# HS_SW.net
KiCad netlist of a schematic drawn in Altium Designer
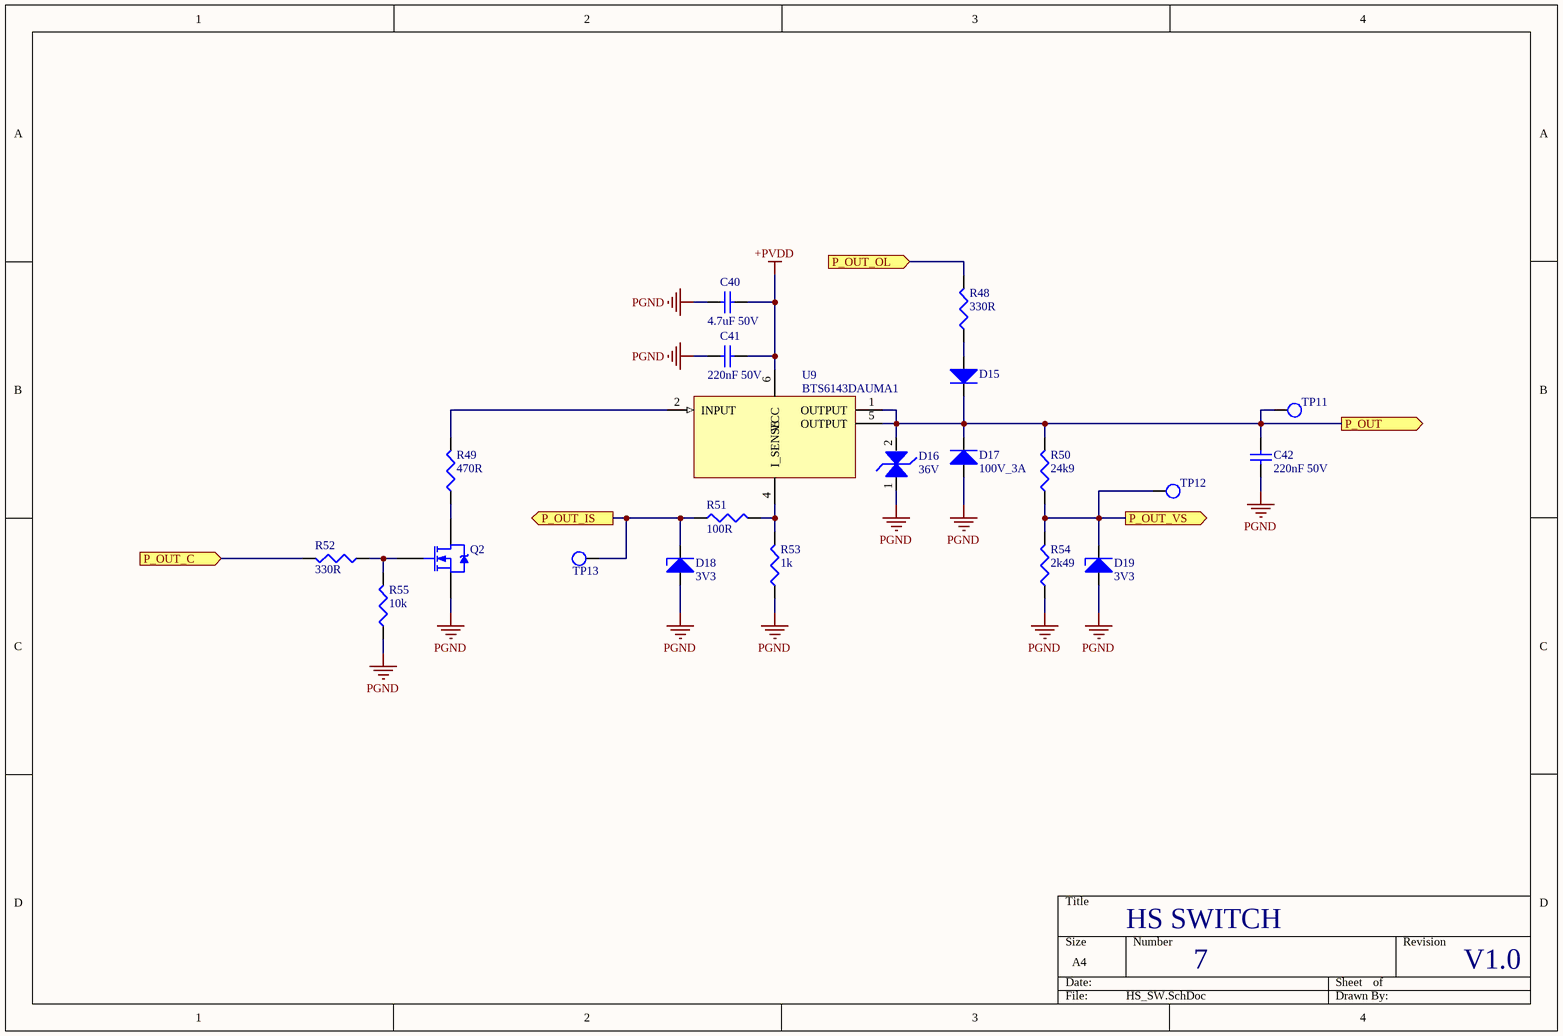
[diagram p0: HS_SW.SchDoc]

(export (version "E")
  (design (tool "Eeschema 10.0.6"))
  (components
    (comp (ref "C40")
      (value "4.7uF 50V")
      (footprint "CAP1206")
      (description "CAP CER 4.7UF 50V %20 X7R 1206")
      (libsource (lib "CAP_Library") (part "CAP1206_4.7uF"))
    )
    (comp (ref "C41")
      (value "220nF 50V")
      (footprint "CAP1206")
      (description "CAP CER 0.22UF 50V X7R 1206")
      (libsource (lib "CAP_Library") (part "CAP1206_220nF"))
    )
    (comp (ref "C42")
      (value "220nF 50V")
      (footprint "CAP1206")
      (description "CAP CER 0.22UF 50V X7R 1206")
      (libsource (lib "CAP_Library") (part "CAP1206_220nF"))
    )
    (comp (ref "D15")
      (value "100V 300mA")
      (footprint "SOD123_1N4148W-7-F")
      (description "DIODE GEN PURP 100V 300MA SOD123")
      (libsource (lib "DIODE_Library") (part "DIODE_1N4148W-7-F"))
    )
    (comp (ref "D16")
      (value "36V")
      (footprint "DO214AA")
      (description "TVS DIODE 36V DO214AA")
      (libsource (lib "DIODE_Library") (part "SMBJ36CA-TR_TVS_BI_DIR"))
    )
    (comp (ref "D17")
      (value "100V_3A")
      (footprint "DO-221A")
      (description "DIODE FRED 100V 3A DO-221AD")
      (libsource (lib "DIODE_Library") (part "FRED_VS-3EYH01-M3/H_100V_3A"))
    )
    (comp (ref "D18")
      (value "3V3")
      (footprint "SOD323")
      (description "DIODE ZENER 3.3V 300MW SOD323")
      (libsource (lib "DIODE_Library") (part "ZENER_3V3_MM3Z3V3T1G"))
    )
    (comp (ref "D19")
      (value "3V3")
      (footprint "SOD323")
      (description "DIODE ZENER 3.3V 300MW SOD323")
      (libsource (lib "DIODE_Library") (part "ZENER_3V3_MM3Z3V3T1G"))
    )
    (comp (ref "Q2")
      (value "60V 360mA")
      (footprint "SOT23_2N7002")
      (description "MOSFET N-CH 60V 0.36A SOT-23")
      (libsource (lib "Mosfet_Library") (part "2N7002P,215_NMOS_60V"))
    )
    (comp (ref "R48")
      (value "330R")
      (footprint "RES0603")
      (description "RES 330 OHM 1% 1/10W 0603")
      (libsource (lib "RES_Library") (part "RES0603_330R"))
    )
    (comp (ref "R49")
      (value "470R")
      (footprint "RES0603")
      (description "RES SMD 470 OHM 1% 1/10W 0603")
      (libsource (lib "RES_Library") (part "RES0603_470R"))
    )
    (comp (ref "R50")
      (value "24k9")
      (footprint "RES0603")
      (description "RES SMD 24.9K OHM 1% 1/10W 0603")
      (libsource (lib "RES_Library") (part "RES0603_24k9"))
    )
    (comp (ref "R51")
      (value "100R")
      (footprint "RES0603")
      (description "RES SMD 100R OHM 1% 1/10W 0603")
      (libsource (lib "RES_Library") (part "RES0603_100R"))
    )
    (comp (ref "R52")
      (value "330R")
      (footprint "RES0603")
      (description "RES 330 OHM 1% 1/10W 0603")
      (libsource (lib "RES_Library") (part "RES0603_330R"))
    )
    (comp (ref "R53")
      (value "1k")
      (footprint "RES0603")
      (description "RES SMD 1K OHM 1% 1/10W 0603")
      (libsource (lib "RES_Library") (part "RES0603_1k"))
    )
    (comp (ref "R54")
      (value "2k49")
      (footprint "RES0603")
      (description "RES 2.49K OHM 1% 1/10W 0603")
      (libsource (lib "RES_Library") (part "RES0603_2k49"))
    )
    (comp (ref "R55")
      (value "10k")
      (footprint "RES0603")
      (description "RES SMD 10K OHM 5% 1/10W 0603")
      (libsource (lib "RES_Library") (part "RES0603_10k"))
    )
    (comp (ref "TP11")
      (value "TEST_POINT")
      (footprint "TEST_POINT_TH")
      (libsource (lib "MISC_Library") (part "TEST_POINT"))
    )
    (comp (ref "TP12")
      (value "TEST_POINT")
      (footprint "TEST_POINT_TH")
      (libsource (lib "MISC_Library") (part "TEST_POINT"))
    )
    (comp (ref "TP13")
      (value "TEST_POINT")
      (footprint "TEST_POINT_TH")
      (libsource (lib "MISC_Library") (part "TEST_POINT"))
    )
    (comp (ref "U9")
      (value "33A")
      (footprint "TO252-5")
      (description "IC HIGH SIDE PWR SWITCH DPAK-5")
      (fields (field (name "P/N") "BTS6143DAUMA1"))
      (libsource (lib "IC_Library") (part "PD_SW_BTS6143DAUMA1"))
    )
  )
  (nets
    (net (code "1") (name "+PVDD") (class "Default")
      (node (ref "C40") (pin "2") (pinfunction "2_2") (pintype "passive"))
      (node (ref "C41") (pin "1") (pinfunction "1_1") (pintype "passive"))
      (node (ref "U9") (pin "6") (pinfunction "VCC_6") (pintype "power_in"))
    )
    (net (code "2") (name "/P_OUT") (class "Default")
      (node (ref "C42") (pin "2") (pinfunction "2_2") (pintype "passive"))
      (node (ref "D15") (pin "2") (pinfunction "K_2") (pintype "passive"))
      (node (ref "D16") (pin "2") (pinfunction "2_2") (pintype "passive"))
      (node (ref "D17") (pin "1") (pinfunction "K_1") (pintype "passive"))
      (node (ref "R50") (pin "2") (pinfunction "2_2") (pintype "passive"))
      (node (ref "TP11") (pin "1") (pinfunction "1_1") (pintype "passive"))
      (node (ref "U9") (pin "1") (pinfunction "OUTPUT_1") (pintype "passive"))
      (node (ref "U9") (pin "5") (pinfunction "OUTPUT_5") (pintype "passive"))
    )
    (net (code "3") (name "/P_OUT_C") (class "Default")
      (node (ref "R52") (pin "2") (pinfunction "2_2") (pintype "passive"))
    )
    (net (code "4") (name "/P_OUT_IS") (class "Default")
      (node (ref "D18") (pin "1") (pinfunction "K_1") (pintype "passive"))
      (node (ref "R51") (pin "1") (pinfunction "1_1") (pintype "passive"))
      (node (ref "TP13") (pin "1") (pinfunction "1_1") (pintype "passive"))
    )
    (net (code "5") (name "/P_OUT_OL") (class "Default")
      (node (ref "R48") (pin "2") (pinfunction "2_2") (pintype "passive"))
    )
    (net (code "6") (name "/P_OUT_VS") (class "Default")
      (node (ref "D19") (pin "1") (pinfunction "K_1") (pintype "passive"))
      (node (ref "R50") (pin "1") (pinfunction "1_1") (pintype "passive"))
      (node (ref "R54") (pin "2") (pinfunction "2_2") (pintype "passive"))
      (node (ref "TP12") (pin "1") (pinfunction "1_1") (pintype "passive"))
    )
    (net (code "7") (name "Net-(D15-A)") (class "Default")
      (node (ref "D15") (pin "1") (pinfunction "A_1") (pintype "passive"))
      (node (ref "R48") (pin "1") (pinfunction "1_1") (pintype "passive"))
    )
    (net (code "8") (name "Net-(Q2-D)") (class "Default")
      (node (ref "Q2") (pin "3") (pinfunction "D_3") (pintype "passive"))
      (node (ref "R49") (pin "1") (pinfunction "1_1") (pintype "passive"))
    )
    (net (code "9") (name "Net-(Q2-G)") (class "Default")
      (node (ref "Q2") (pin "1") (pinfunction "G_1") (pintype "passive"))
      (node (ref "R52") (pin "1") (pinfunction "1_1") (pintype "passive"))
      (node (ref "R55") (pin "2") (pinfunction "2_2") (pintype "passive"))
    )
    (net (code "10") (name "Net-(U9-INPUT)") (class "Default")
      (node (ref "R49") (pin "2") (pinfunction "2_2") (pintype "passive"))
      (node (ref "U9") (pin "2") (pinfunction "INPUT_2") (pintype "input"))
    )
    (net (code "11") (name "Net-(U9-I_SENSE)") (class "Default")
      (node (ref "R51") (pin "2") (pinfunction "2_2") (pintype "passive"))
      (node (ref "R53") (pin "2") (pinfunction "2_2") (pintype "passive"))
      (node (ref "U9") (pin "4") (pinfunction "I_SENSE_4") (pintype "power_in"))
    )
    (net (code "12") (name "PGND") (class "Default")
      (node (ref "C40") (pin "1") (pinfunction "1_1") (pintype "passive"))
      (node (ref "C41") (pin "2") (pinfunction "2_2") (pintype "passive"))
      (node (ref "C42") (pin "1") (pinfunction "1_1") (pintype "passive"))
      (node (ref "D16") (pin "1") (pinfunction "1_1") (pintype "passive"))
      (node (ref "D17") (pin "2") (pinfunction "A_2") (pintype "passive"))
      (node (ref "D18") (pin "2") (pinfunction "A_2") (pintype "passive"))
      (node (ref "D19") (pin "2") (pinfunction "A_2") (pintype "passive"))
      (node (ref "Q2") (pin "2") (pinfunction "S_2") (pintype "passive"))
      (node (ref "R53") (pin "1") (pinfunction "1_1") (pintype "passive"))
      (node (ref "R54") (pin "1") (pinfunction "1_1") (pintype "passive"))
      (node (ref "R55") (pin "1") (pinfunction "1_1") (pintype "passive"))
    )
  )
)
